# esmsx.net
KiCad netlist of a schematic drawn in EAGLE
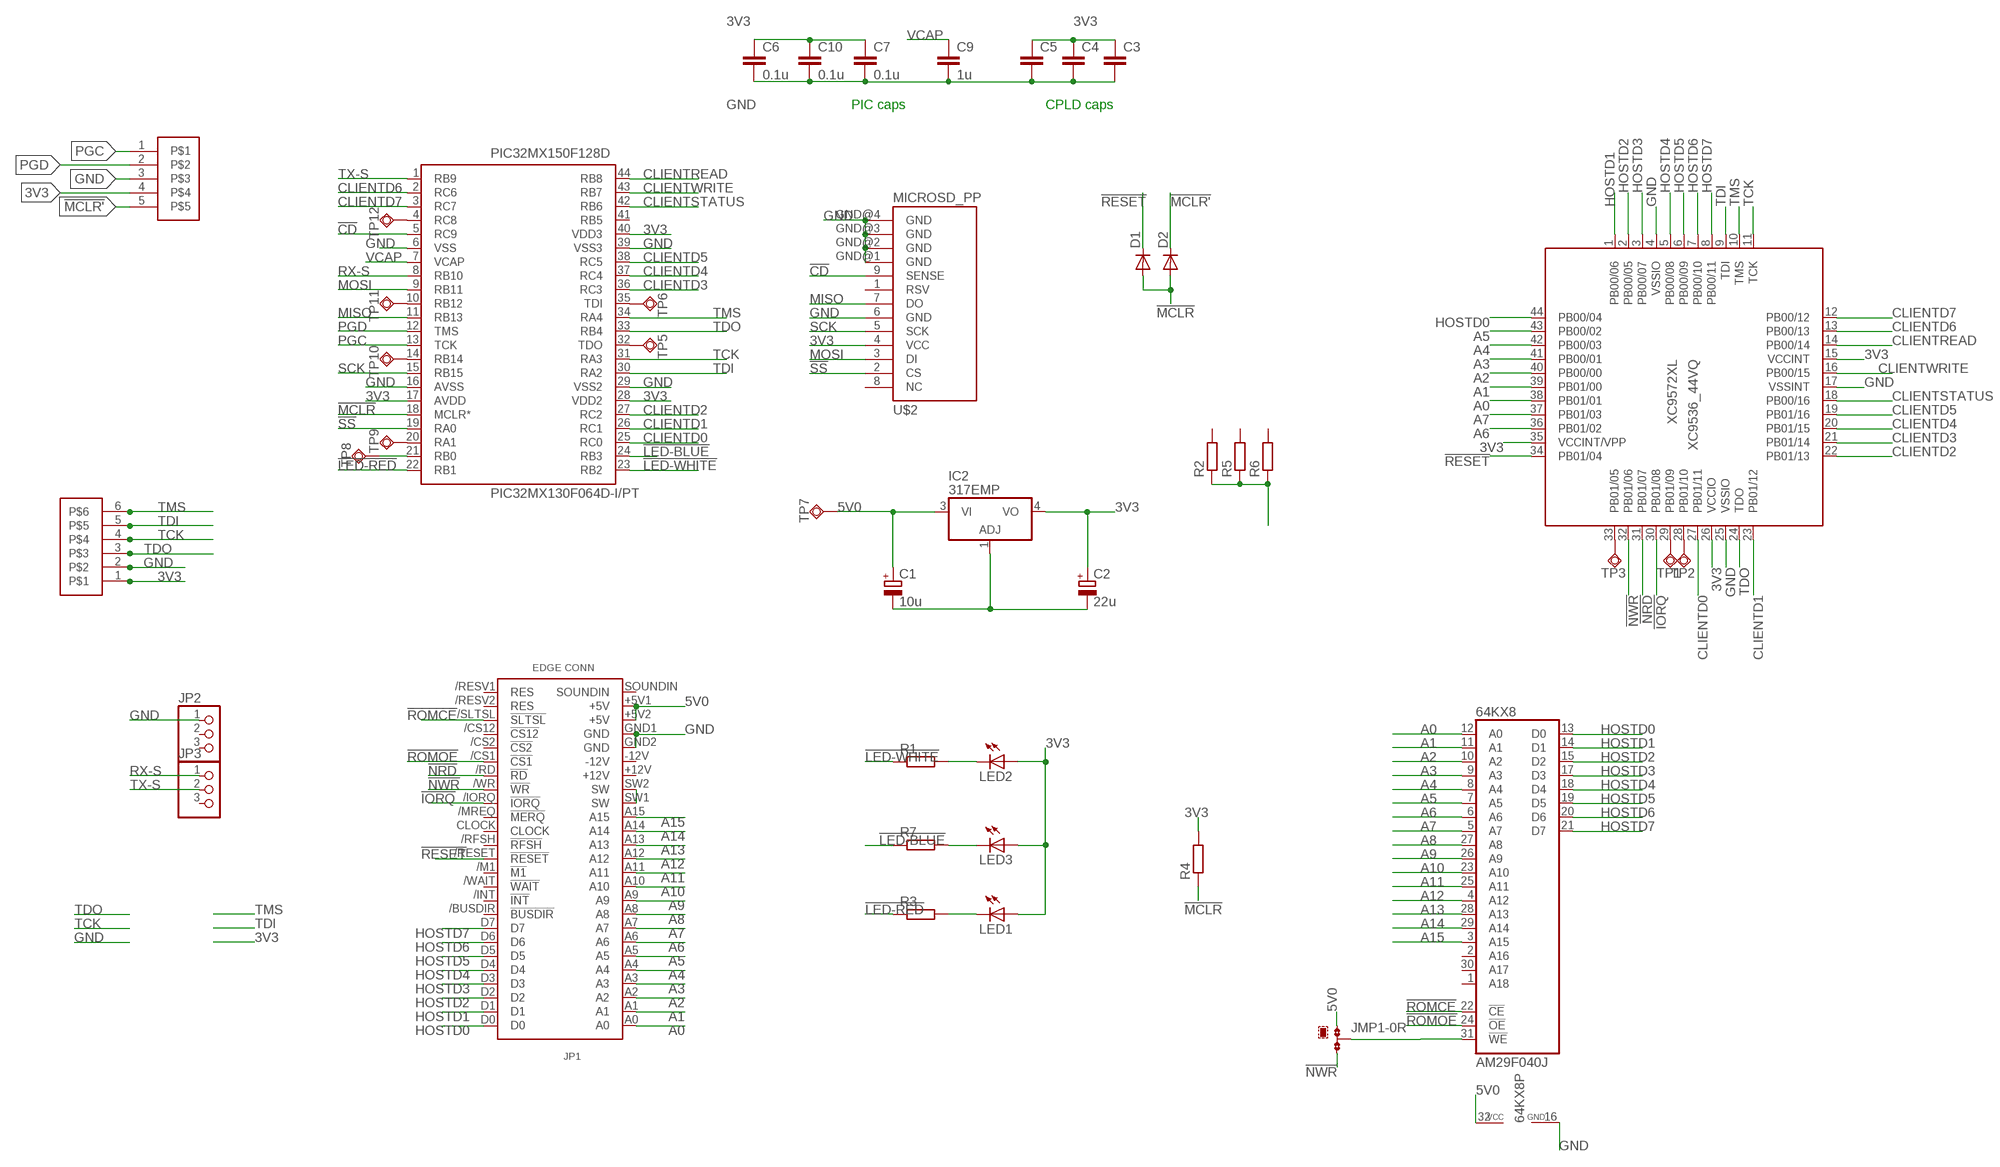
[diagram p0: schematic, sheet 1]

(export (version "E")
  (design (tool "Eeschema 10.0.6"))
  (components
    (comp (ref "64KX8")
      (value "AM29F040J")
      (footprint "eagle-import:PLCC32R")
      (libsource (lib "eagle-import") (part "AM29F040J"))
    )
    (comp (ref "C1")
      (value "10u")
      (footprint "eagle-import:SMC_B")
      (libsource (lib "eagle-import") (part "CPOL-EUSMCB"))
    )
    (comp (ref "C2")
      (value "22u")
      (footprint "eagle-import:SMC_B")
      (libsource (lib "eagle-import") (part "CPOL-EUSMCB"))
    )
    (comp (ref "C3")
      (value "C-EUC0805")
      (footprint "eagle-import:C0805")
      (libsource (lib "eagle-import") (part "C-EUC0805"))
    )
    (comp (ref "C4")
      (value "C-EUC0805")
      (footprint "eagle-import:C0805")
      (libsource (lib "eagle-import") (part "C-EUC0805"))
    )
    (comp (ref "C5")
      (value "C-EUC0805")
      (footprint "eagle-import:C0805")
      (libsource (lib "eagle-import") (part "C-EUC0805"))
    )
    (comp (ref "C6")
      (value "0.1u")
      (footprint "eagle-import:C0805")
      (libsource (lib "eagle-import") (part "rcl_334_C-EUC0805"))
    )
    (comp (ref "C7")
      (value "0.1u")
      (footprint "eagle-import:C0805")
      (libsource (lib "eagle-import") (part "C-EUC0805"))
    )
    (comp (ref "C9")
      (value "1u")
      (footprint "eagle-import:C0805")
      (libsource (lib "eagle-import") (part "C-EUC0805"))
    )
    (comp (ref "C10")
      (value "0.1u")
      (footprint "eagle-import:C0805")
      (libsource (lib "eagle-import") (part "C-EUC0805"))
    )
    (comp (ref "D1")
      (value "DIODE-SOD123")
      (footprint "eagle-import:SOD123")
      (libsource (lib "eagle-import") (part "DIODE-SOD123"))
    )
    (comp (ref "D2")
      (value "DIODE-SOD123")
      (footprint "eagle-import:SOD123")
      (libsource (lib "eagle-import") (part "DIODE-SOD123"))
    )
    (comp (ref "IC2")
      (value "317EMP")
      (footprint "eagle-import:SOT223")
      (libsource (lib "eagle-import") (part "317EMP"))
    )
    (comp (ref "JMP1")
      (value "0R-JUMPA")
      (footprint "eagle-import:A0R-JMP")
      (libsource (lib "eagle-import") (part "0R-JUMPA"))
    )
    (comp (ref "JP1")
      (value "MSXCART")
      (footprint "eagle-import:MSXCART")
      (libsource (lib "eagle-import") (part "MSXCART"))
    )
    (comp (ref "JP2")
      (value "PINHD-1X3")
      (footprint "eagle-import:1X03")
      (libsource (lib "eagle-import") (part "PINHD-1X3"))
    )
    (comp (ref "JP3")
      (value "PINHD-1X3")
      (footprint "eagle-import:1X03")
      (libsource (lib "eagle-import") (part "PINHD-1X3"))
    )
    (comp (ref "LED1")
      (value "LEDCHIPLED_1206")
      (footprint "eagle-import:CHIPLED_1206")
      (libsource (lib "eagle-import") (part "LEDCHIPLED_1206"))
    )
    (comp (ref "LED2")
      (value "LEDCHIPLED_1206")
      (footprint "eagle-import:CHIPLED_1206")
      (libsource (lib "eagle-import") (part "LEDCHIPLED_1206"))
    )
    (comp (ref "LED3")
      (value "LEDCHIPLED_1206")
      (footprint "eagle-import:CHIPLED_1206")
      (libsource (lib "eagle-import") (part "LEDCHIPLED_1206"))
    )
    (comp (ref "PIC32MX150F128D")
      (value "PIC32MX130F064D-I/PT")
      (footprint "eagle-import:QFP80P1200X1200X120-44N")
      (fields (field (name "MPN") "PIC32MX130F064D-I/PT "))
      (libsource (lib "eagle-import") (part "PIC32MX130F064D-I/PT"))
    )
    (comp (ref "R1")
      (value "R-EU_R0805W")
      (footprint "eagle-import:R0805W")
      (libsource (lib "eagle-import") (part "resistor_R-EU_R0805W"))
    )
    (comp (ref "R2")
      (value "R-EU_R0805W")
      (footprint "eagle-import:R0805W")
      (libsource (lib "eagle-import") (part "resistor_R-EU_R0805W"))
    )
    (comp (ref "R3")
      (value "R-EU_R0805W")
      (footprint "eagle-import:R0805W")
      (libsource (lib "eagle-import") (part "resistor_R-EU_R0805W"))
    )
    (comp (ref "R4")
      (value "R-EU_R0805W")
      (footprint "eagle-import:R0805W")
      (libsource (lib "eagle-import") (part "R-EU_R0805W"))
    )
    (comp (ref "R5")
      (value "R-EU_R0805W")
      (footprint "eagle-import:R0805W")
      (libsource (lib "eagle-import") (part "resistor_R-EU_R0805W"))
    )
    (comp (ref "R6")
      (value "R-EU_R0805W")
      (footprint "eagle-import:R0805W")
      (libsource (lib "eagle-import") (part "resistor_R-EU_R0805W"))
    )
    (comp (ref "R7")
      (value "R-EU_R0805W")
      (footprint "eagle-import:R0805W")
      (libsource (lib "eagle-import") (part "resistor_R-EU_R0805W"))
    )
    (comp (ref "TP1")
      (value "TPSQTP20SQ")
      (footprint "eagle-import:TP20SQ")
      (libsource (lib "eagle-import") (part "TPSQTP20SQ"))
    )
    (comp (ref "TP2")
      (value "TPSQTP20SQ")
      (footprint "eagle-import:TP20SQ")
      (libsource (lib "eagle-import") (part "TPSQTP20SQ"))
    )
    (comp (ref "TP3")
      (value "TPSQTP20SQ")
      (footprint "eagle-import:TP20SQ")
      (libsource (lib "eagle-import") (part "TPSQTP20SQ"))
    )
    (comp (ref "TP5")
      (value "TPSQTP20SQ")
      (footprint "eagle-import:TP20SQ")
      (libsource (lib "eagle-import") (part "TPSQTP20SQ"))
    )
    (comp (ref "TP6")
      (value "TPSQTP20SQ")
      (footprint "eagle-import:TP20SQ")
      (libsource (lib "eagle-import") (part "TPSQTP20SQ"))
    )
    (comp (ref "TP7")
      (value "TPSQTP20SQ")
      (footprint "eagle-import:TP20SQ")
      (libsource (lib "eagle-import") (part "TPSQTP20SQ"))
    )
    (comp (ref "TP8")
      (value "TPSQTP20SQ")
      (footprint "eagle-import:TP20SQ")
      (libsource (lib "eagle-import") (part "TPSQTP20SQ"))
    )
    (comp (ref "TP9")
      (value "TPSQTP20SQ")
      (footprint "eagle-import:TP20SQ")
      (libsource (lib "eagle-import") (part "TPSQTP20SQ"))
    )
    (comp (ref "TP10")
      (value "TPSQTP20SQ")
      (footprint "eagle-import:TP20SQ")
      (libsource (lib "eagle-import") (part "TPSQTP20SQ"))
    )
    (comp (ref "TP11")
      (value "TPSQTP20SQ")
      (footprint "eagle-import:TP20SQ")
      (libsource (lib "eagle-import") (part "TPSQTP20SQ"))
    )
    (comp (ref "TP12")
      (value "TPSQTP20SQ")
      (footprint "eagle-import:TP20SQ")
      (libsource (lib "eagle-import") (part "TPSQTP20SQ"))
    )
    (comp (ref "U$2")
      (value "MICROSD_PP")
      (footprint "eagle-import:MICROSD_PP")
      (libsource (lib "eagle-import") (part "MICROSD_PP"))
    )
    (comp (ref "U$3")
      (value "6PIN")
      (footprint "eagle-import:1X04-1.27MM")
      (libsource (lib "eagle-import") (part "6PIN"))
    )
    (comp (ref "U$4")
      (value "5PIN")
      (footprint "eagle-import:1X05-1.27MM")
      (libsource (lib "eagle-import") (part "5PIN"))
    )
    (comp (ref "XC9572XL")
      (value "XC9536_44VQ")
      (footprint "eagle-import:SQFP-S-10X10-44")
      (fields (field (name "MPN") "XC9536-15VQG44C"))
      (libsource (lib "eagle-import") (part "XC9536_44VQ"))
    )
  )
  (nets
    (net (code "1") (name "/+12V") (class "Default")
      (node (ref "JP1") (pin "+12V") (pinfunction "+12V_+12V") (pintype "power_in"))
    )
    (net (code "2") (name "/-12V") (class "Default")
      (node (ref "JP1") (pin "-12V") (pinfunction "-12V_-12V") (pintype "power_in"))
    )
    (net (code "3") (name "/5V0") (class "Default")
      (node (ref "64KX8") (pin "31") (pinfunction "~{WE}_31") (pintype "input"))
      (node (ref "64KX8") (pin "32") (pinfunction "VCC_32") (pintype "power_in"))
      (node (ref "C1") (pin "+") (pinfunction "+_+") (pintype "passive"))
      (node (ref "IC2") (pin "3") (pinfunction "VI_3") (pintype "input"))
      (node (ref "JMP1") (pin "1") (pinfunction "1_1") (pintype "passive"))
      (node (ref "JMP1") (pin "2") (pinfunction "2_2") (pintype "passive"))
      (node (ref "JP1") (pin "+5V1") (pinfunction "+5V_+5V1") (pintype "power_in"))
      (node (ref "JP1") (pin "+5V2") (pinfunction "+5V_+5V2") (pintype "power_in"))
      (node (ref "R2") (pin "1") (pinfunction "1_1") (pintype "passive"))
      (node (ref "R5") (pin "1") (pinfunction "1_1") (pintype "passive"))
      (node (ref "R6") (pin "1") (pinfunction "1_1") (pintype "passive"))
      (node (ref "TP7") (pin "TP") (pinfunction "TP_TP") (pintype "input"))
    )
    (net (code "4") (name "/A0") (class "Default")
      (node (ref "64KX8") (pin "12") (pinfunction "A0_12") (pintype "input"))
      (node (ref "JP1") (pin "A0") (pinfunction "A0_A0") (pintype "output"))
      (node (ref "XC9572XL") (pin "38") (pinfunction "PB01/01_38") (pintype "bidirectional"))
    )
    (net (code "5") (name "/A1") (class "Default")
      (node (ref "64KX8") (pin "11") (pinfunction "A1_11") (pintype "input"))
      (node (ref "JP1") (pin "A1") (pinfunction "A1_A1") (pintype "output"))
      (node (ref "XC9572XL") (pin "39") (pinfunction "PB01/00_39") (pintype "bidirectional"))
    )
    (net (code "6") (name "/A2") (class "Default")
      (node (ref "64KX8") (pin "10") (pinfunction "A2_10") (pintype "input"))
      (node (ref "JP1") (pin "A2") (pinfunction "A2_A2") (pintype "output"))
      (node (ref "XC9572XL") (pin "40") (pinfunction "PB00/00_40") (pintype "bidirectional"))
    )
    (net (code "7") (name "/A3") (class "Default")
      (node (ref "64KX8") (pin "9") (pinfunction "A3_9") (pintype "input"))
      (node (ref "JP1") (pin "A3") (pinfunction "A3_A3") (pintype "output"))
      (node (ref "XC9572XL") (pin "41") (pinfunction "PB00/01_41") (pintype "bidirectional"))
    )
    (net (code "8") (name "/A4") (class "Default")
      (node (ref "64KX8") (pin "8") (pinfunction "A4_8") (pintype "input"))
      (node (ref "JP1") (pin "A4") (pinfunction "A4_A4") (pintype "output"))
      (node (ref "XC9572XL") (pin "42") (pinfunction "PB00/03_42") (pintype "bidirectional"))
    )
    (net (code "9") (name "/A5") (class "Default")
      (node (ref "64KX8") (pin "7") (pinfunction "A5_7") (pintype "input"))
      (node (ref "JP1") (pin "A5") (pinfunction "A5_A5") (pintype "output"))
      (node (ref "XC9572XL") (pin "43") (pinfunction "PB00/02_43") (pintype "bidirectional"))
    )
    (net (code "10") (name "/A6") (class "Default")
      (node (ref "64KX8") (pin "6") (pinfunction "A6_6") (pintype "input"))
      (node (ref "JP1") (pin "A6") (pinfunction "A6_A6") (pintype "output"))
      (node (ref "XC9572XL") (pin "36") (pinfunction "PB01/02_36") (pintype "bidirectional"))
    )
    (net (code "11") (name "/A7") (class "Default")
      (node (ref "64KX8") (pin "5") (pinfunction "A7_5") (pintype "input"))
      (node (ref "JP1") (pin "A7") (pinfunction "A7_A7") (pintype "output"))
      (node (ref "XC9572XL") (pin "37") (pinfunction "PB01/03_37") (pintype "bidirectional"))
    )
    (net (code "12") (name "/A8") (class "Default")
      (node (ref "64KX8") (pin "27") (pinfunction "A8_27") (pintype "input"))
      (node (ref "JP1") (pin "A8") (pinfunction "A8_A8") (pintype "output"))
    )
    (net (code "13") (name "/A9") (class "Default")
      (node (ref "64KX8") (pin "26") (pinfunction "A9_26") (pintype "input"))
      (node (ref "JP1") (pin "A9") (pinfunction "A9_A9") (pintype "output"))
    )
    (net (code "14") (name "/A10") (class "Default")
      (node (ref "64KX8") (pin "23") (pinfunction "A10_23") (pintype "input"))
      (node (ref "JP1") (pin "A10") (pinfunction "A10_A10") (pintype "output"))
    )
    (net (code "15") (name "/A11") (class "Default")
      (node (ref "64KX8") (pin "25") (pinfunction "A11_25") (pintype "input"))
      (node (ref "JP1") (pin "A11") (pinfunction "A11_A11") (pintype "output"))
    )
    (net (code "16") (name "/A12") (class "Default")
      (node (ref "64KX8") (pin "4") (pinfunction "A12_4") (pintype "input"))
      (node (ref "JP1") (pin "A12") (pinfunction "A12_A12") (pintype "output"))
    )
    (net (code "17") (name "/A13") (class "Default")
      (node (ref "64KX8") (pin "28") (pinfunction "A13_28") (pintype "input"))
      (node (ref "JP1") (pin "A13") (pinfunction "A13_A13") (pintype "output"))
    )
    (net (code "18") (name "/A14") (class "Default")
      (node (ref "64KX8") (pin "29") (pinfunction "A14_29") (pintype "input"))
      (node (ref "JP1") (pin "A14") (pinfunction "A14_A14") (pintype "output"))
    )
    (net (code "19") (name "/A15") (class "Default")
      (node (ref "64KX8") (pin "3") (pinfunction "A15_3") (pintype "input"))
      (node (ref "JP1") (pin "A15") (pinfunction "A15_A15") (pintype "output"))
    )
    (net (code "20") (name "/CLIENTD0") (class "Default")
      (node (ref "PIC32MX150F128D") (pin "25") (pinfunction "RC0_25") (pintype "bidirectional"))
      (node (ref "XC9572XL") (pin "27") (pinfunction "PB01/11_27") (pintype "bidirectional"))
    )
    (net (code "21") (name "/CLIENTD1") (class "Default")
      (node (ref "PIC32MX150F128D") (pin "26") (pinfunction "RC1_26") (pintype "bidirectional"))
      (node (ref "XC9572XL") (pin "23") (pinfunction "PB01/12_23") (pintype "bidirectional"))
    )
    (net (code "22") (name "/CLIENTD2") (class "Default")
      (node (ref "PIC32MX150F128D") (pin "27") (pinfunction "RC2_27") (pintype "bidirectional"))
      (node (ref "XC9572XL") (pin "22") (pinfunction "PB01/13_22") (pintype "bidirectional"))
    )
    (net (code "23") (name "/CLIENTD3") (class "Default")
      (node (ref "PIC32MX150F128D") (pin "36") (pinfunction "RC3_36") (pintype "bidirectional"))
      (node (ref "XC9572XL") (pin "21") (pinfunction "PB01/14_21") (pintype "bidirectional"))
    )
    (net (code "24") (name "/CLIENTD4") (class "Default")
      (node (ref "PIC32MX150F128D") (pin "37") (pinfunction "RC4_37") (pintype "bidirectional"))
      (node (ref "XC9572XL") (pin "20") (pinfunction "PB01/15_20") (pintype "bidirectional"))
    )
    (net (code "25") (name "/CLIENTD5") (class "Default")
      (node (ref "PIC32MX150F128D") (pin "38") (pinfunction "RC5_38") (pintype "bidirectional"))
      (node (ref "XC9572XL") (pin "19") (pinfunction "PB01/16_19") (pintype "bidirectional"))
    )
    (net (code "26") (name "/CLIENTD6") (class "Default")
      (node (ref "PIC32MX150F128D") (pin "2") (pinfunction "RC6_2") (pintype "bidirectional"))
      (node (ref "XC9572XL") (pin "13") (pinfunction "PB00/13_13") (pintype "bidirectional"))
    )
    (net (code "27") (name "/CLIENTD7") (class "Default")
      (node (ref "PIC32MX150F128D") (pin "3") (pinfunction "RC7_3") (pintype "bidirectional"))
      (node (ref "XC9572XL") (pin "12") (pinfunction "PB00/12_12") (pintype "bidirectional"))
    )
    (net (code "28") (name "/CLIENTREAD") (class "Default")
      (node (ref "PIC32MX150F128D") (pin "44") (pinfunction "RB8_44") (pintype "bidirectional"))
      (node (ref "XC9572XL") (pin "14") (pinfunction "PB00/14_14") (pintype "bidirectional"))
    )
    (net (code "29") (name "/CLIENTSTATUS") (class "Default")
      (node (ref "PIC32MX150F128D") (pin "42") (pinfunction "RB6_42") (pintype "bidirectional"))
      (node (ref "XC9572XL") (pin "18") (pinfunction "PB00/16_18") (pintype "bidirectional"))
    )
    (net (code "30") (name "/CLIENTWRITE") (class "Default")
      (node (ref "PIC32MX150F128D") (pin "43") (pinfunction "RB7_43") (pintype "bidirectional"))
      (node (ref "XC9572XL") (pin "16") (pinfunction "PB00/15_16") (pintype "bidirectional"))
    )
    (net (code "31") (name "/HOSTD0") (class "Default")
      (node (ref "64KX8") (pin "13") (pinfunction "D0_13") (pintype "tri_state"))
      (node (ref "JP1") (pin "D0") (pinfunction "D0_D0") (pintype "bidirectional"))
      (node (ref "XC9572XL") (pin "44") (pinfunction "PB00/04_44") (pintype "bidirectional"))
    )
    (net (code "32") (name "/HOSTD1") (class "Default")
      (node (ref "64KX8") (pin "14") (pinfunction "D1_14") (pintype "tri_state"))
      (node (ref "JP1") (pin "D1") (pinfunction "D1_D1") (pintype "bidirectional"))
      (node (ref "XC9572XL") (pin "1") (pinfunction "PB00/06_1") (pintype "bidirectional"))
    )
    (net (code "33") (name "/HOSTD2") (class "Default")
      (node (ref "64KX8") (pin "15") (pinfunction "D2_15") (pintype "tri_state"))
      (node (ref "JP1") (pin "D2") (pinfunction "D2_D2") (pintype "bidirectional"))
      (node (ref "XC9572XL") (pin "2") (pinfunction "PB00/05_2") (pintype "bidirectional"))
    )
    (net (code "34") (name "/HOSTD3") (class "Default")
      (node (ref "64KX8") (pin "17") (pinfunction "D3_17") (pintype "tri_state"))
      (node (ref "JP1") (pin "D3") (pinfunction "D3_D3") (pintype "bidirectional"))
      (node (ref "XC9572XL") (pin "3") (pinfunction "PB00/07_3") (pintype "bidirectional"))
    )
    (net (code "35") (name "/HOSTD4") (class "Default")
      (node (ref "64KX8") (pin "18") (pinfunction "D4_18") (pintype "tri_state"))
      (node (ref "JP1") (pin "D4") (pinfunction "D4_D4") (pintype "bidirectional"))
      (node (ref "XC9572XL") (pin "5") (pinfunction "PB00/08_5") (pintype "bidirectional"))
    )
    (net (code "36") (name "/HOSTD5") (class "Default")
      (node (ref "64KX8") (pin "19") (pinfunction "D5_19") (pintype "tri_state"))
      (node (ref "JP1") (pin "D5") (pinfunction "D5_D5") (pintype "bidirectional"))
      (node (ref "XC9572XL") (pin "6") (pinfunction "PB00/09_6") (pintype "bidirectional"))
    )
    (net (code "37") (name "/HOSTD6") (class "Default")
      (node (ref "64KX8") (pin "20") (pinfunction "D6_20") (pintype "tri_state"))
      (node (ref "JP1") (pin "D6") (pinfunction "D6_D6") (pintype "bidirectional"))
      (node (ref "XC9572XL") (pin "7") (pinfunction "PB00/10_7") (pintype "bidirectional"))
    )
    (net (code "38") (name "/HOSTD7") (class "Default")
      (node (ref "64KX8") (pin "21") (pinfunction "D7_21") (pintype "tri_state"))
      (node (ref "JP1") (pin "D7") (pinfunction "D7_D7") (pintype "bidirectional"))
      (node (ref "XC9572XL") (pin "8") (pinfunction "PB00/11_8") (pintype "bidirectional"))
    )
    (net (code "39") (name "/MISO") (class "Default")
      (node (ref "PIC32MX150F128D") (pin "11") (pinfunction "RB13_11") (pintype "bidirectional"))
      (node (ref "U$2") (pin "7") (pinfunction "DO_7") (pintype "bidirectional"))
    )
    (net (code "40") (name "/MOSI") (class "Default")
      (node (ref "PIC32MX150F128D") (pin "9") (pinfunction "RB11_9") (pintype "bidirectional"))
      (node (ref "U$2") (pin "3") (pinfunction "DI_3") (pintype "bidirectional"))
    )
    (net (code "41") (name "/RX-S") (class "Default")
      (node (ref "JP3") (pin "1") (pinfunction "1_1") (pintype "passive"))
      (node (ref "PIC32MX150F128D") (pin "8") (pinfunction "RB10_8") (pintype "bidirectional"))
    )
    (net (code "42") (name "/SCK") (class "Default")
      (node (ref "PIC32MX150F128D") (pin "15") (pinfunction "RB15_15") (pintype "bidirectional"))
      (node (ref "U$2") (pin "5") (pinfunction "SCK_5") (pintype "bidirectional"))
    )
    (net (code "43") (name "/TCK") (class "Default")
      (node (ref "PIC32MX150F128D") (pin "31") (pinfunction "RA3_31") (pintype "bidirectional"))
      (node (ref "U$3") (pin "4") (pinfunction "P$4_4") (pintype "bidirectional"))
      (node (ref "XC9572XL") (pin "11") (pinfunction "TCK_11") (pintype "input"))
    )
    (net (code "44") (name "/TDI") (class "Default")
      (node (ref "PIC32MX150F128D") (pin "30") (pinfunction "RA2_30") (pintype "bidirectional"))
      (node (ref "U$3") (pin "5") (pinfunction "P$5_5") (pintype "bidirectional"))
      (node (ref "XC9572XL") (pin "9") (pinfunction "TDI_9") (pintype "input"))
    )
    (net (code "45") (name "/TDO") (class "Default")
      (node (ref "PIC32MX150F128D") (pin "33") (pinfunction "RB4_33") (pintype "bidirectional"))
      (node (ref "U$3") (pin "3") (pinfunction "P$3_3") (pintype "bidirectional"))
      (node (ref "XC9572XL") (pin "24") (pinfunction "TDO_24") (pintype "output"))
    )
    (net (code "46") (name "/TMS") (class "Default")
      (node (ref "PIC32MX150F128D") (pin "34") (pinfunction "RA4_34") (pintype "bidirectional"))
      (node (ref "U$3") (pin "6") (pinfunction "P$6_6") (pintype "bidirectional"))
      (node (ref "XC9572XL") (pin "10") (pinfunction "TMS_10") (pintype "input"))
    )
    (net (code "47") (name "/TX-S") (class "Default")
      (node (ref "JP3") (pin "2") (pinfunction "2_2") (pintype "passive"))
      (node (ref "PIC32MX150F128D") (pin "1") (pinfunction "RB9_1") (pintype "bidirectional"))
    )
    (net (code "48") (name "/VCAP") (class "Default")
      (node (ref "C9") (pin "1") (pinfunction "1_1") (pintype "passive"))
      (node (ref "PIC32MX150F128D") (pin "7") (pinfunction "VCAP_7") (pintype "bidirectional"))
    )
    (net (code "49") (name "/~{CD}") (class "Default")
      (node (ref "PIC32MX150F128D") (pin "5") (pinfunction "RC9_5") (pintype "bidirectional"))
      (node (ref "U$2") (pin "9") (pinfunction "SENSE_9") (pintype "bidirectional"))
    )
    (net (code "50") (name "/~{IORQ}") (class "Default")
      (node (ref "JP1") (pin "/IORQ") (pinfunction "~{IORQ}_/IORQ") (pintype "output"))
      (node (ref "XC9572XL") (pin "30") (pinfunction "PB01/08_30") (pintype "bidirectional"))
    )
    (net (code "51") (name "/~{LED-BLUE}") (class "Default")
      (node (ref "PIC32MX150F128D") (pin "24") (pinfunction "RB3_24") (pintype "bidirectional"))
      (node (ref "R7") (pin "1") (pinfunction "1_1") (pintype "passive"))
    )
    (net (code "52") (name "/~{LED-RED}") (class "Default")
      (node (ref "PIC32MX150F128D") (pin "22") (pinfunction "RB1_22") (pintype "bidirectional"))
      (node (ref "R3") (pin "1") (pinfunction "1_1") (pintype "passive"))
    )
    (net (code "53") (name "/~{LED-WHITE}") (class "Default")
      (node (ref "PIC32MX150F128D") (pin "23") (pinfunction "RB2_23") (pintype "bidirectional"))
      (node (ref "R1") (pin "1") (pinfunction "1_1") (pintype "passive"))
    )
    (net (code "54") (name "/~{MCLR'}") (class "Default")
      (node (ref "D2") (pin "C") (pinfunction "C_C") (pintype "passive"))
      (node (ref "U$4") (pin "5") (pinfunction "P$5_5") (pintype "bidirectional"))
    )
    (net (code "55") (name "/~{MCLR}") (class "Default")
      (node (ref "D1") (pin "A") (pinfunction "A_A") (pintype "passive"))
      (node (ref "D2") (pin "A") (pinfunction "A_A") (pintype "passive"))
      (node (ref "PIC32MX150F128D") (pin "18") (pinfunction "MCLR*_18") (pintype "input"))
      (node (ref "R4") (pin "1") (pinfunction "1_1") (pintype "passive"))
    )
    (net (code "56") (name "/~{NRD}") (class "Default")
      (node (ref "JP1") (pin "/RD") (pinfunction "~{RD}_/RD") (pintype "output"))
      (node (ref "XC9572XL") (pin "31") (pinfunction "PB01/07_31") (pintype "bidirectional"))
    )
    (net (code "57") (name "/~{NWR}") (class "Default")
      (node (ref "JMP1") (pin "3") (pinfunction "3_3") (pintype "passive"))
      (node (ref "JP1") (pin "/WR") (pinfunction "~{WR}_/WR") (pintype "output"))
      (node (ref "XC9572XL") (pin "32") (pinfunction "PB01/06_32") (pintype "bidirectional"))
    )
    (net (code "58") (name "/~{RESET}") (class "Default")
      (node (ref "D1") (pin "C") (pinfunction "C_C") (pintype "passive"))
      (node (ref "JP1") (pin "/RESET") (pinfunction "~{RESET}_/RESET") (pintype "output"))
      (node (ref "XC9572XL") (pin "34") (pinfunction "PB01/04_34") (pintype "bidirectional"))
    )
    (net (code "59") (name "/~{ROMCE}") (class "Default")
      (node (ref "64KX8") (pin "22") (pinfunction "~{CE}_22") (pintype "input"))
      (node (ref "JP1") (pin "/SLTSL") (pinfunction "~{SLTSL}_/SLTSL") (pintype "output"))
    )
    (net (code "60") (name "/~{ROMOE}") (class "Default")
      (node (ref "64KX8") (pin "24") (pinfunction "~{OE}_24") (pintype "input"))
      (node (ref "JP1") (pin "/CS1") (pinfunction "~{CS1}_/CS1") (pintype "output"))
    )
    (net (code "61") (name "/~{SS}") (class "Default")
      (node (ref "PIC32MX150F128D") (pin "19") (pinfunction "RA0_19") (pintype "bidirectional"))
      (node (ref "U$2") (pin "2") (pinfunction "CS_2") (pintype "bidirectional"))
    )
    (net (code "62") (name "3V3") (class "Default")
      (node (ref "C10") (pin "1") (pinfunction "1_1") (pintype "passive"))
      (node (ref "C2") (pin "+") (pinfunction "+_+") (pintype "passive"))
      (node (ref "C3") (pin "1") (pinfunction "1_1") (pintype "passive"))
      (node (ref "C4") (pin "1") (pinfunction "1_1") (pintype "passive"))
      (node (ref "C5") (pin "1") (pinfunction "1_1") (pintype "passive"))
      (node (ref "C6") (pin "1") (pinfunction "1_1") (pintype "passive"))
      (node (ref "C7") (pin "1") (pinfunction "1_1") (pintype "passive"))
      (node (ref "IC2") (pin "4") (pinfunction "VO_4") (pintype "passive"))
      (node (ref "LED1") (pin "A") (pinfunction "A_A") (pintype "passive"))
      (node (ref "LED2") (pin "A") (pinfunction "A_A") (pintype "passive"))
      (node (ref "LED3") (pin "A") (pinfunction "A_A") (pintype "passive"))
      (node (ref "PIC32MX150F128D") (pin "17") (pinfunction "AVDD_17") (pintype "power_in"))
      (node (ref "PIC32MX150F128D") (pin "28") (pinfunction "VDD2_28") (pintype "power_in"))
      (node (ref "PIC32MX150F128D") (pin "40") (pinfunction "VDD3_40") (pintype "power_in"))
      (node (ref "R4") (pin "2") (pinfunction "2_2") (pintype "passive"))
      (node (ref "U$2") (pin "4") (pinfunction "VCC_4") (pintype "bidirectional"))
      (node (ref "U$3") (pin "1") (pinfunction "P$1_1") (pintype "bidirectional"))
      (node (ref "U$4") (pin "4") (pinfunction "P$4_4") (pintype "bidirectional"))
      (node (ref "XC9572XL") (pin "15") (pinfunction "VCCINT_15") (pintype "power_in"))
      (node (ref "XC9572XL") (pin "26") (pinfunction "VCCIO_26") (pintype "power_in"))
      (node (ref "XC9572XL") (pin "35") (pinfunction "VCCINT/VPP_35") (pintype "input"))
    )
    (net (code "63") (name "GND") (class "Default")
      (node (ref "64KX8") (pin "16") (pinfunction "GND_16") (pintype "power_in"))
      (node (ref "C1") (pin "-") (pinfunction "-_-") (pintype "passive"))
      (node (ref "C10") (pin "2") (pinfunction "2_2") (pintype "passive"))
      (node (ref "C2") (pin "-") (pinfunction "-_-") (pintype "passive"))
      (node (ref "C3") (pin "2") (pinfunction "2_2") (pintype "passive"))
      (node (ref "C4") (pin "2") (pinfunction "2_2") (pintype "passive"))
      (node (ref "C5") (pin "2") (pinfunction "2_2") (pintype "passive"))
      (node (ref "C6") (pin "2") (pinfunction "2_2") (pintype "passive"))
      (node (ref "C7") (pin "2") (pinfunction "2_2") (pintype "passive"))
      (node (ref "C9") (pin "2") (pinfunction "2_2") (pintype "passive"))
      (node (ref "IC2") (pin "1") (pinfunction "ADJ_1") (pintype "input"))
      (node (ref "JP1") (pin "GND1") (pinfunction "GND_GND1") (pintype "power_in"))
      (node (ref "JP1") (pin "GND2") (pinfunction "GND_GND2") (pintype "power_in"))
      (node (ref "JP2") (pin "1") (pinfunction "1_1") (pintype "passive"))
      (node (ref "PIC32MX150F128D") (pin "16") (pinfunction "AVSS_16") (pintype "power_in"))
      (node (ref "PIC32MX150F128D") (pin "29") (pinfunction "VSS2_29") (pintype "power_in"))
      (node (ref "PIC32MX150F128D") (pin "39") (pinfunction "VSS3_39") (pintype "power_in"))
      (node (ref "PIC32MX150F128D") (pin "6") (pinfunction "VSS_6") (pintype "power_in"))
      (node (ref "U$2") (pin "6") (pinfunction "GND_6") (pintype "bidirectional"))
      (node (ref "U$2") (pin "GND@1") (pinfunction "GND_GND@1") (pintype "bidirectional"))
      (node (ref "U$2") (pin "GND@2") (pinfunction "GND_GND@2") (pintype "bidirectional"))
      (node (ref "U$2") (pin "GND@3") (pinfunction "GND_GND@3") (pintype "bidirectional"))
      (node (ref "U$2") (pin "GND@4") (pinfunction "GND_GND@4") (pintype "bidirectional"))
      (node (ref "U$3") (pin "2") (pinfunction "P$2_2") (pintype "bidirectional"))
      (node (ref "U$4") (pin "3") (pinfunction "P$3_3") (pintype "bidirectional"))
      (node (ref "XC9572XL") (pin "17") (pinfunction "VSSINT_17") (pintype "power_in"))
      (node (ref "XC9572XL") (pin "25") (pinfunction "VSSIO_25") (pintype "power_in"))
      (node (ref "XC9572XL") (pin "4") (pinfunction "VSSIO_4") (pintype "power_in"))
    )
    (net (code "64") (name "Net-(JP1-SW-PadSW1)") (class "Default")
      (node (ref "JP1") (pin "SW1") (pinfunction "SW_SW1") (pintype "passive"))
      (node (ref "JP1") (pin "SW2") (pinfunction "SW_SW2") (pintype "passive"))
    )
    (net (code "65") (name "Net-(LED1-PadC)") (class "Default")
      (node (ref "LED1") (pin "C") (pinfunction "C_C") (pintype "passive"))
      (node (ref "R3") (pin "2") (pinfunction "2_2") (pintype "passive"))
    )
    (net (code "66") (name "Net-(LED2-PadC)") (class "Default")
      (node (ref "LED2") (pin "C") (pinfunction "C_C") (pintype "passive"))
      (node (ref "R1") (pin "2") (pinfunction "2_2") (pintype "passive"))
    )
    (net (code "67") (name "Net-(LED3-PadC)") (class "Default")
      (node (ref "LED3") (pin "C") (pinfunction "C_C") (pintype "passive"))
      (node (ref "R7") (pin "2") (pinfunction "2_2") (pintype "passive"))
    )
    (net (code "68") (name "Net-(PIC32MX150F128D-RA1)") (class "Default")
      (node (ref "PIC32MX150F128D") (pin "20") (pinfunction "RA1_20") (pintype "bidirectional"))
      (node (ref "TP9") (pin "TP") (pinfunction "TP_TP") (pintype "input"))
    )
    (net (code "69") (name "Net-(PIC32MX150F128D-RB0)") (class "Default")
      (node (ref "PIC32MX150F128D") (pin "21") (pinfunction "RB0_21") (pintype "bidirectional"))
      (node (ref "TP8") (pin "TP") (pinfunction "TP_TP") (pintype "input"))
    )
    (net (code "70") (name "Net-(PIC32MX150F128D-RB12)") (class "Default")
      (node (ref "PIC32MX150F128D") (pin "10") (pinfunction "RB12_10") (pintype "passive"))
      (node (ref "TP11") (pin "TP") (pinfunction "TP_TP") (pintype "input"))
    )
    (net (code "71") (name "Net-(PIC32MX150F128D-RB14)") (class "Default")
      (node (ref "PIC32MX150F128D") (pin "14") (pinfunction "RB14_14") (pintype "bidirectional"))
      (node (ref "TP10") (pin "TP") (pinfunction "TP_TP") (pintype "input"))
    )
    (net (code "72") (name "Net-(PIC32MX150F128D-RC8)") (class "Default")
      (node (ref "PIC32MX150F128D") (pin "4") (pinfunction "RC8_4") (pintype "bidirectional"))
      (node (ref "TP12") (pin "TP") (pinfunction "TP_TP") (pintype "input"))
    )
    (net (code "73") (name "Net-(PIC32MX150F128D-TDI)") (class "Default")
      (node (ref "PIC32MX150F128D") (pin "35") (pinfunction "TDI_35") (pintype "input"))
      (node (ref "TP6") (pin "TP") (pinfunction "TP_TP") (pintype "input"))
    )
    (net (code "74") (name "Net-(PIC32MX150F128D-TDO)") (class "Default")
      (node (ref "PIC32MX150F128D") (pin "32") (pinfunction "TDO_32") (pintype "output"))
      (node (ref "TP5") (pin "TP") (pinfunction "TP_TP") (pintype "input"))
    )
    (net (code "75") (name "Net-(XC9572XL-PB01{slash}05)") (class "Default")
      (node (ref "TP3") (pin "TP") (pinfunction "TP_TP") (pintype "input"))
      (node (ref "XC9572XL") (pin "33") (pinfunction "PB01/05_33") (pintype "bidirectional"))
    )
    (net (code "76") (name "Net-(XC9572XL-PB01{slash}09)") (class "Default")
      (node (ref "TP1") (pin "TP") (pinfunction "TP_TP") (pintype "input"))
      (node (ref "XC9572XL") (pin "29") (pinfunction "PB01/09_29") (pintype "bidirectional"))
    )
    (net (code "77") (name "Net-(XC9572XL-PB01{slash}10)") (class "Default")
      (node (ref "TP2") (pin "TP") (pinfunction "TP_TP") (pintype "input"))
      (node (ref "XC9572XL") (pin "28") (pinfunction "PB01/10_28") (pintype "bidirectional"))
    )
    (net (code "78") (name "PGC") (class "Default")
      (node (ref "PIC32MX150F128D") (pin "13") (pinfunction "TCK_13") (pintype "input"))
      (node (ref "U$4") (pin "1") (pinfunction "P$1_1") (pintype "bidirectional"))
    )
    (net (code "79") (name "PGD") (class "Default")
      (node (ref "PIC32MX150F128D") (pin "12") (pinfunction "TMS_12") (pintype "input"))
      (node (ref "U$4") (pin "2") (pinfunction "P$2_2") (pintype "bidirectional"))
    )
    (net (code "80") (name "unconnected-(64KX8A-A16-Pad2)") (class "Default")
      (node (ref "64KX8") (pin "2") (pinfunction "A16_2") (pintype "input"))
    )
    (net (code "81") (name "unconnected-(64KX8A-A17-Pad30)") (class "Default")
      (node (ref "64KX8") (pin "30") (pinfunction "A17_30") (pintype "input"))
    )
    (net (code "82") (name "unconnected-(64KX8A-A18-Pad1)") (class "Default")
      (node (ref "64KX8") (pin "1") (pinfunction "A18_1") (pintype "input"))
    )
    (net (code "83") (name "unconnected-(JP1-PadCLOCK)") (class "Default")
      (node (ref "JP1") (pin "CLOCK") (pinfunction "CLOCK_CLOCK") (pintype "output"))
    )
    (net (code "84") (name "unconnected-(JP1-PadSOUNDIN)") (class "Default")
      (node (ref "JP1") (pin "SOUNDIN") (pinfunction "SOUNDIN_SOUNDIN") (pintype "passive"))
    )
    (net (code "85") (name "unconnected-(JP1-RES-Pad{slash}RESV1)") (class "Default")
      (node (ref "JP1") (pin "/RESV1") (pinfunction "RES_/RESV1") (pintype "no_connect"))
    )
    (net (code "86") (name "unconnected-(JP1-RES-Pad{slash}RESV2)") (class "Default")
      (node (ref "JP1") (pin "/RESV2") (pinfunction "RES_/RESV2") (pintype "no_connect"))
    )
    (net (code "87") (name "unconnected-(JP1-~{BUSDIR}-Pad{slash}BUSDIR)") (class "Default")
      (node (ref "JP1") (pin "/BUSDIR") (pinfunction "~{BUSDIR}_/BUSDIR") (pintype "input"))
    )
    (net (code "88") (name "unconnected-(JP1-~{CS2}-Pad{slash}CS2)") (class "Default")
      (node (ref "JP1") (pin "/CS2") (pinfunction "~{CS2}_/CS2") (pintype "output"))
    )
    (net (code "89") (name "unconnected-(JP1-~{CS12}-Pad{slash}CS12)") (class "Default")
      (node (ref "JP1") (pin "/CS12") (pinfunction "~{CS12}_/CS12") (pintype "output"))
    )
    (net (code "90") (name "unconnected-(JP1-~{INT}-Pad{slash}INT)") (class "Default")
      (node (ref "JP1") (pin "/INT") (pinfunction "~{INT}_/INT") (pintype "open_collector"))
    )
    (net (code "91") (name "unconnected-(JP1-~{M1}-Pad{slash}M1)") (class "Default")
      (node (ref "JP1") (pin "/M1") (pinfunction "~{M1}_/M1") (pintype "output"))
    )
    (net (code "92") (name "unconnected-(JP1-~{MERQ}-Pad{slash}MREQ)") (class "Default")
      (node (ref "JP1") (pin "/MREQ") (pinfunction "~{MERQ}_/MREQ") (pintype "output"))
    )
    (net (code "93") (name "unconnected-(JP1-~{RFSH}-Pad{slash}RFSH)") (class "Default")
      (node (ref "JP1") (pin "/RFSH") (pinfunction "~{RFSH}_/RFSH") (pintype "output"))
    )
    (net (code "94") (name "unconnected-(JP1-~{WAIT}-Pad{slash}WAIT)") (class "Default")
      (node (ref "JP1") (pin "/WAIT") (pinfunction "~{WAIT}_/WAIT") (pintype "open_collector"))
    )
    (net (code "95") (name "unconnected-(JP2-Pad2)") (class "Default")
      (node (ref "JP2") (pin "2") (pinfunction "2_2") (pintype "passive"))
    )
    (net (code "96") (name "unconnected-(JP2-Pad3)") (class "Default")
      (node (ref "JP2") (pin "3") (pinfunction "3_3") (pintype "passive"))
    )
    (net (code "97") (name "unconnected-(JP3-Pad3)") (class "Default")
      (node (ref "JP3") (pin "3") (pinfunction "3_3") (pintype "passive"))
    )
    (net (code "98") (name "unconnected-(PIC32MX150F128D-RB5-Pad41)") (class "Default")
      (node (ref "PIC32MX150F128D") (pin "41") (pinfunction "RB5_41") (pintype "bidirectional"))
    )
    (net (code "99") (name "unconnected-(R2-Pad2)") (class "Default")
      (node (ref "R2") (pin "2") (pinfunction "2_2") (pintype "passive"))
    )
    (net (code "100") (name "unconnected-(R5-Pad2)") (class "Default")
      (node (ref "R5") (pin "2") (pinfunction "2_2") (pintype "passive"))
    )
    (net (code "101") (name "unconnected-(R6-Pad2)") (class "Default")
      (node (ref "R6") (pin "2") (pinfunction "2_2") (pintype "passive"))
    )
    (net (code "102") (name "unconnected-(U$2-NC-Pad8)") (class "Default")
      (node (ref "U$2") (pin "8") (pinfunction "NC_8") (pintype "bidirectional"))
    )
    (net (code "103") (name "unconnected-(U$2-RSV-Pad1)") (class "Default")
      (node (ref "U$2") (pin "1") (pinfunction "RSV_1") (pintype "bidirectional"))
    )
  )
)
